# MPU9250-IMU_I2C_V2.net
KiCad netlist of a schematic drawn in EAGLE
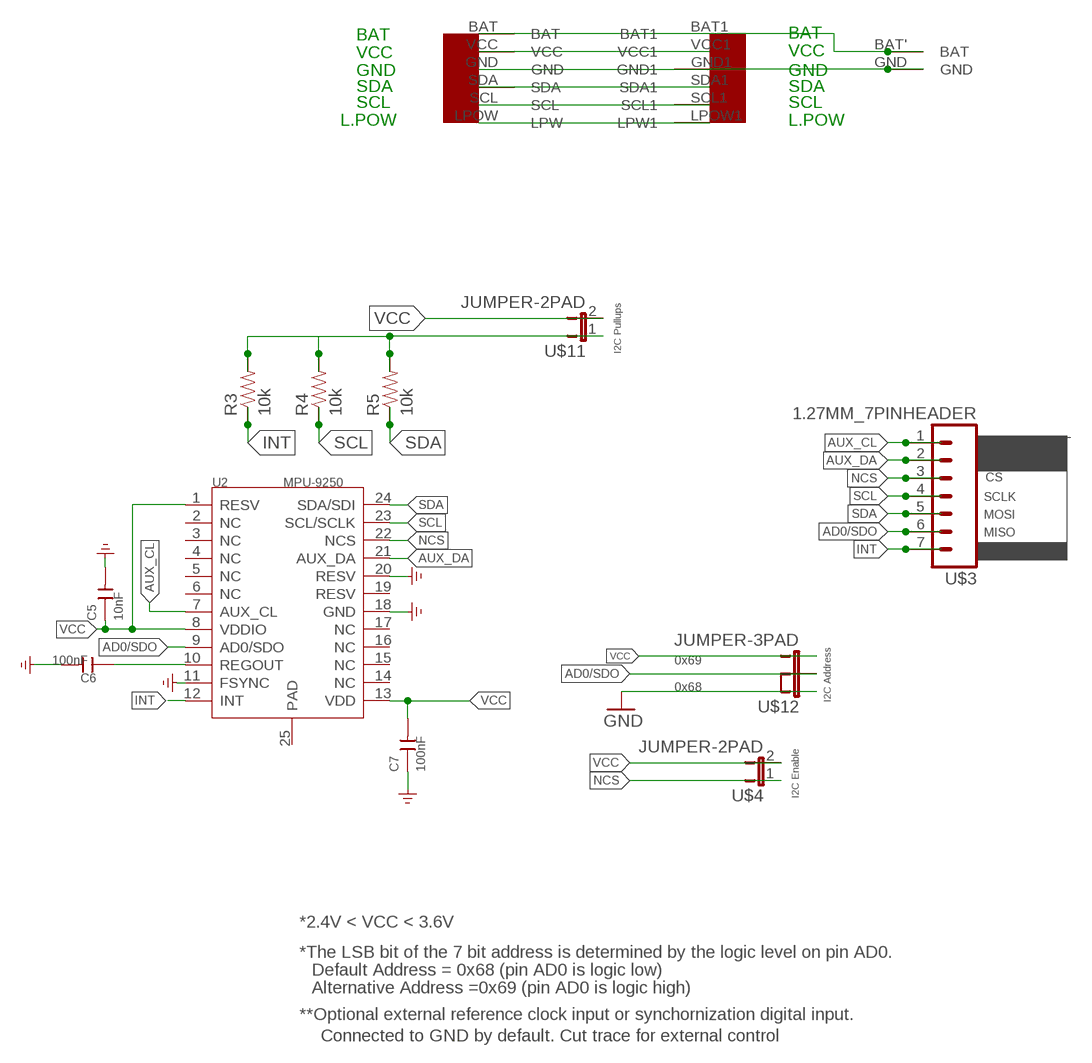
[diagram p0: schematic, sheet 1]

(export (version "E")
  (design (tool "Eeschema 10.0.6"))
  (components
    (comp (ref "C5")
      (value "10nF")
      (footprint "eagle-import:C0603")
      (libsource (lib "eagle-import") (part "CAP-0603"))
    )
    (comp (ref "C6")
      (value "100nF")
      (footprint "eagle-import:C0603")
      (libsource (lib "eagle-import") (part "CAP-0603"))
    )
    (comp (ref "C7")
      (value "100nF")
      (footprint "eagle-import:C0603")
      (libsource (lib "eagle-import") (part "CAP-0603"))
    )
    (comp (ref "R3")
      (value "10k")
      (footprint "eagle-import:0402-RES")
      (libsource (lib "eagle-import") (part "RESISTOR0402-RES"))
    )
    (comp (ref "R4")
      (value "10k")
      (footprint "eagle-import:0402-RES")
      (libsource (lib "eagle-import") (part "RESISTOR0402-RES"))
    )
    (comp (ref "R5")
      (value "10k")
      (footprint "eagle-import:0402-RES")
      (libsource (lib "eagle-import") (part "RESISTOR0402-RES"))
    )
    (comp (ref "U$1")
      (value "EZ-I2CHEADERV1")
      (footprint "eagle-import:EZ-I2CHEADERV1")
      (libsource (lib "eagle-import") (part "EZ-I2CHEADERV1"))
    )
    (comp (ref "U$3")
      (value "1.27MM_7PINHEADER")
      (footprint "eagle-import:1.27MM_7PINHEADER")
      (libsource (lib "eagle-import") (part "1.27MM_7PINHEADER"))
    )
    (comp (ref "U$4")
      (value "JUMPER-2PAD")
      (footprint "eagle-import:JUMPER-2PAD")
      (libsource (lib "eagle-import") (part "JUMPER-2PAD"))
    )
    (comp (ref "U$10")
      (value "MINI_BATTERY_HOLES")
      (footprint "eagle-import:MINI_BATTERY_HOLES")
      (libsource (lib "eagle-import") (part "MINI_BATTERY_HOLES"))
    )
    (comp (ref "U$11")
      (value "JUMPER-2PAD")
      (footprint "eagle-import:JUMPER-2PAD")
      (libsource (lib "eagle-import") (part "JUMPER-2PAD"))
    )
    (comp (ref "U$12")
      (value "JUMPER-3PAD")
      (footprint "eagle-import:JUMPER-3PAD")
      (libsource (lib "eagle-import") (part "JUMPER-3PAD"))
    )
    (comp (ref "U2")
      (value "MPU-9250")
      (footprint "eagle-import:LEAD-QFN24")
      (libsource (lib "eagle-import") (part "MPU-9250"))
    )
  )
  (nets
    (net (code "1") (name "AD0{slash}SDO") (class "Default")
      (node (ref "U$12") (pin "2") (pinfunction "2_2") (pintype "passive"))
      (node (ref "U$3") (pin "6") (pinfunction "6_6") (pintype "passive"))
      (node (ref "U2") (pin "9") (pinfunction "AD0/SDO_9") (pintype "bidirectional"))
    )
    (net (code "2") (name "AUX_CL") (class "Default")
      (node (ref "U$3") (pin "1") (pinfunction "1_1") (pintype "passive"))
      (node (ref "U2") (pin "7") (pinfunction "AUX_CL_7") (pintype "bidirectional"))
    )
    (net (code "3") (name "AUX_DA") (class "Default")
      (node (ref "U$3") (pin "2") (pinfunction "2_2") (pintype "passive"))
      (node (ref "U2") (pin "21") (pinfunction "AUX_DA_21") (pintype "bidirectional"))
    )
    (net (code "4") (name "GND") (class "Default")
      (node (ref "C5") (pin "2") (pinfunction "2_2") (pintype "passive"))
      (node (ref "C6") (pin "2") (pinfunction "2_2") (pintype "passive"))
      (node (ref "C7") (pin "1") (pinfunction "1_1") (pintype "passive"))
      (node (ref "U$1") (pin "GND") (pinfunction "GND_GND") (pintype "bidirectional"))
      (node (ref "U$1") (pin "GND1") (pinfunction "GND1_GND1") (pintype "bidirectional"))
      (node (ref "U$10") (pin "GND") (pinfunction "GND_GND") (pintype "bidirectional"))
      (node (ref "U$12") (pin "1") (pinfunction "1_1") (pintype "passive"))
      (node (ref "U2") (pin "11") (pinfunction "FSYNC_11") (pintype "bidirectional"))
      (node (ref "U2") (pin "18") (pinfunction "GND_18") (pintype "bidirectional"))
      (node (ref "U2") (pin "20") (pinfunction "RESV_20") (pintype "bidirectional"))
    )
    (net (code "5") (name "INT") (class "Default")
      (node (ref "R3") (pin "1") (pinfunction "1_1") (pintype "passive"))
      (node (ref "U$3") (pin "7") (pinfunction "7_7") (pintype "passive"))
      (node (ref "U2") (pin "12") (pinfunction "INT_12") (pintype "bidirectional"))
    )
    (net (code "6") (name "NCS") (class "Default")
      (node (ref "U$3") (pin "3") (pinfunction "3_3") (pintype "passive"))
      (node (ref "U$4") (pin "1") (pinfunction "1_1") (pintype "passive"))
      (node (ref "U2") (pin "22") (pinfunction "NCS_22") (pintype "bidirectional"))
    )
    (net (code "7") (name "Net-(R3-Pad2)") (class "Default")
      (node (ref "R3") (pin "2") (pinfunction "2_2") (pintype "passive"))
      (node (ref "R4") (pin "2") (pinfunction "2_2") (pintype "passive"))
      (node (ref "R5") (pin "2") (pinfunction "2_2") (pintype "passive"))
      (node (ref "U$11") (pin "1") (pinfunction "1_1") (pintype "passive"))
    )
    (net (code "8") (name "Net-(U$1-LPW)") (class "Default")
      (node (ref "U$1") (pin "LPOW") (pinfunction "LPW_LPOW") (pintype "bidirectional"))
      (node (ref "U$1") (pin "LPOW1") (pinfunction "LPW1_LPOW1") (pintype "bidirectional"))
    )
    (net (code "9") (name "Net-(U$10-BAT)") (class "Default")
      (node (ref "U$1") (pin "BAT") (pinfunction "BAT_BAT") (pintype "bidirectional"))
      (node (ref "U$1") (pin "BAT1") (pinfunction "BAT1_BAT1") (pintype "bidirectional"))
      (node (ref "U$10") (pin "BAT'") (pinfunction "BAT_BAT'") (pintype "bidirectional"))
    )
    (net (code "10") (name "Net-(U2-REGOUT)") (class "Default")
      (node (ref "C6") (pin "1") (pinfunction "1_1") (pintype "passive"))
      (node (ref "U2") (pin "10") (pinfunction "REGOUT_10") (pintype "bidirectional"))
    )
    (net (code "11") (name "SCL") (class "Default")
      (node (ref "R4") (pin "1") (pinfunction "1_1") (pintype "passive"))
      (node (ref "U$1") (pin "SCL") (pinfunction "SCL_SCL") (pintype "bidirectional"))
      (node (ref "U$1") (pin "SCL1") (pinfunction "SCL1_SCL1") (pintype "bidirectional"))
      (node (ref "U$3") (pin "4") (pinfunction "4_4") (pintype "passive"))
      (node (ref "U2") (pin "23") (pinfunction "SCL/SCLK_23") (pintype "bidirectional"))
    )
    (net (code "12") (name "SDA") (class "Default")
      (node (ref "R5") (pin "1") (pinfunction "1_1") (pintype "passive"))
      (node (ref "U$1") (pin "SDA") (pinfunction "SDA_SDA") (pintype "bidirectional"))
      (node (ref "U$1") (pin "SDA1") (pinfunction "SDA1_SDA1") (pintype "bidirectional"))
      (node (ref "U$3") (pin "5") (pinfunction "5_5") (pintype "passive"))
      (node (ref "U2") (pin "24") (pinfunction "SDA/SDI_24") (pintype "bidirectional"))
    )
    (net (code "13") (name "VCC") (class "Default")
      (node (ref "C5") (pin "1") (pinfunction "1_1") (pintype "passive"))
      (node (ref "C7") (pin "2") (pinfunction "2_2") (pintype "passive"))
      (node (ref "U$1") (pin "VCC") (pinfunction "VCC_VCC") (pintype "bidirectional"))
      (node (ref "U$1") (pin "VCC1") (pinfunction "VCC1_VCC1") (pintype "bidirectional"))
      (node (ref "U$11") (pin "2") (pinfunction "2_2") (pintype "passive"))
      (node (ref "U$12") (pin "3") (pinfunction "3_3") (pintype "passive"))
      (node (ref "U$4") (pin "2") (pinfunction "2_2") (pintype "passive"))
      (node (ref "U2") (pin "1") (pinfunction "RESV_1") (pintype "bidirectional"))
      (node (ref "U2") (pin "13") (pinfunction "VDD_13") (pintype "bidirectional"))
      (node (ref "U2") (pin "8") (pinfunction "VDDIO_8") (pintype "bidirectional"))
    )
    (net (code "14") (name "unconnected-(U2-NC-Pad2)") (class "Default")
      (node (ref "U2") (pin "2") (pinfunction "NC_2") (pintype "bidirectional"))
    )
    (net (code "15") (name "unconnected-(U2-NC-Pad3)") (class "Default")
      (node (ref "U2") (pin "3") (pinfunction "NC_3") (pintype "bidirectional"))
    )
    (net (code "16") (name "unconnected-(U2-NC-Pad4)") (class "Default")
      (node (ref "U2") (pin "4") (pinfunction "NC_4") (pintype "bidirectional"))
    )
    (net (code "17") (name "unconnected-(U2-NC-Pad5)") (class "Default")
      (node (ref "U2") (pin "5") (pinfunction "NC_5") (pintype "bidirectional"))
    )
    (net (code "18") (name "unconnected-(U2-NC-Pad6)") (class "Default")
      (node (ref "U2") (pin "6") (pinfunction "NC_6") (pintype "bidirectional"))
    )
    (net (code "19") (name "unconnected-(U2-NC-Pad14)") (class "Default")
      (node (ref "U2") (pin "14") (pinfunction "NC_14") (pintype "bidirectional"))
    )
    (net (code "20") (name "unconnected-(U2-NC-Pad15)") (class "Default")
      (node (ref "U2") (pin "15") (pinfunction "NC_15") (pintype "bidirectional"))
    )
    (net (code "21") (name "unconnected-(U2-NC-Pad16)") (class "Default")
      (node (ref "U2") (pin "16") (pinfunction "NC_16") (pintype "bidirectional"))
    )
    (net (code "22") (name "unconnected-(U2-NC-Pad17)") (class "Default")
      (node (ref "U2") (pin "17") (pinfunction "NC_17") (pintype "bidirectional"))
    )
    (net (code "23") (name "unconnected-(U2-PAD-Pad25)") (class "Default")
      (node (ref "U2") (pin "25") (pinfunction "PAD_25") (pintype "bidirectional"))
    )
    (net (code "24") (name "unconnected-(U2-RESV-Pad19)") (class "Default")
      (node (ref "U2") (pin "19") (pinfunction "RESV_19") (pintype "bidirectional"))
    )
  )
)
